# USBHub.net
KiCad netlist of a schematic drawn in Altium Designer
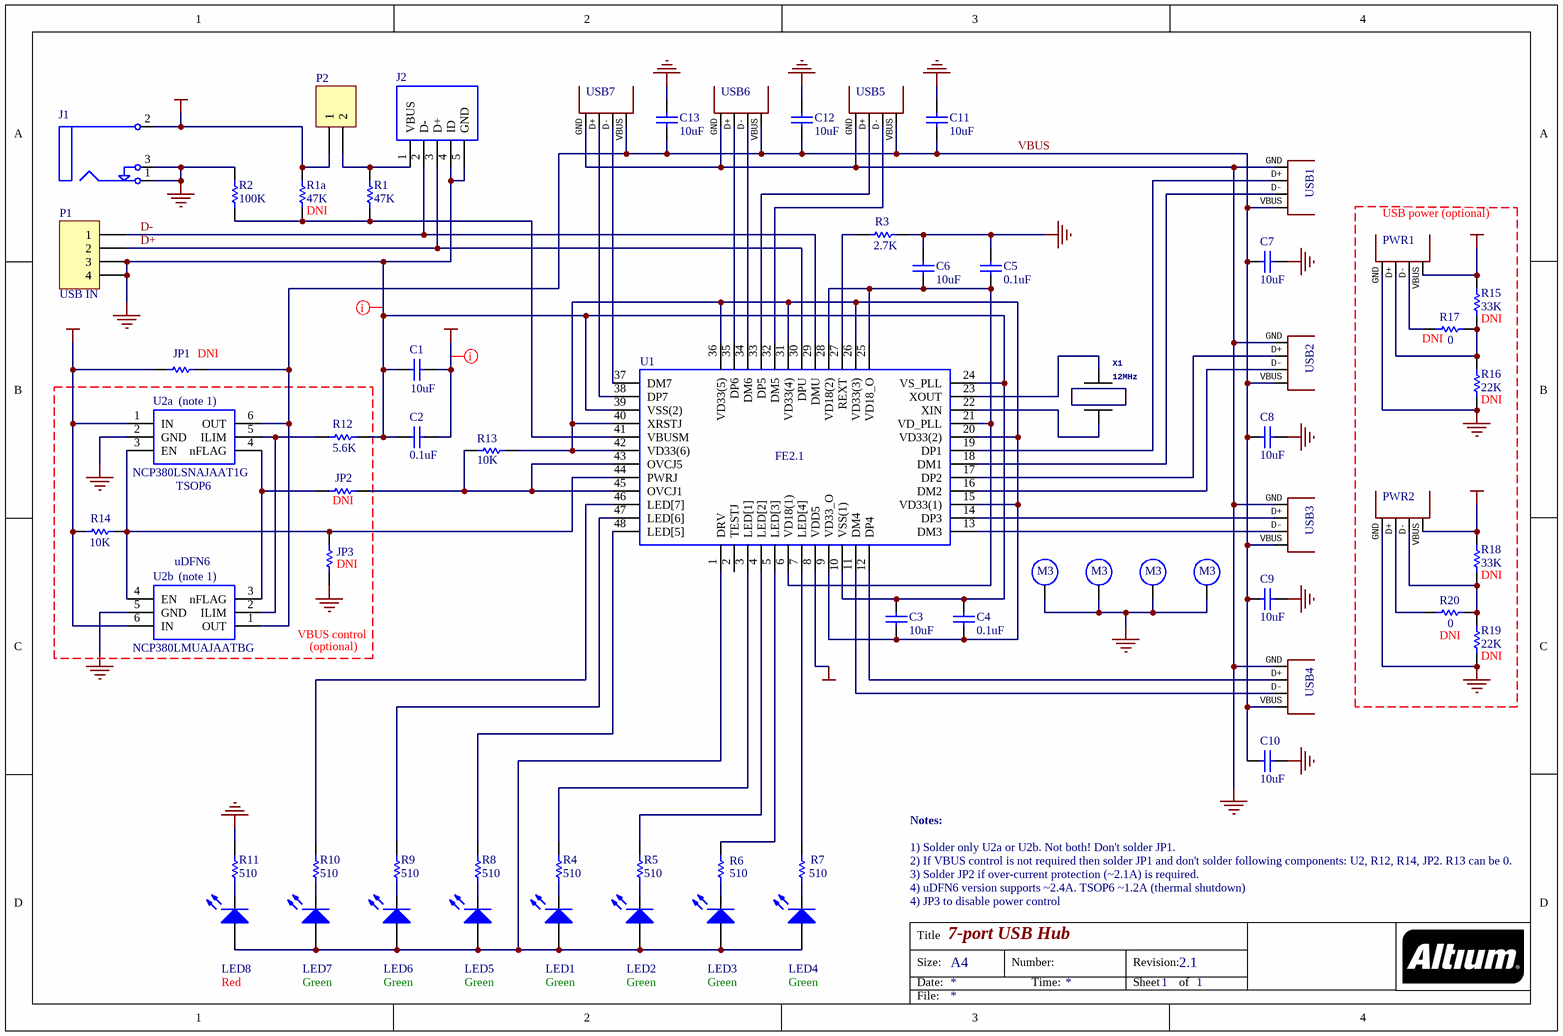
[diagram p0: USBHub.SchDoc]

(export (version "E")
  (design (tool "Eeschema 10.0.6"))
  (components
    (comp (ref "C1")
      (value "10uF")
      (footprint "C0805")
      (description "Ceramic Chip Capacitor - Standard")
      (fields (field (name "Comment") "C0805") (field (name "PUBLISHER") "Altium Limited"))
      (libsource (lib "KEMET Chip Capacitor") (part "C0805"))
    )
    (comp (ref "C2")
      (value "0.1uF")
      (footprint "C0805")
      (description "Ceramic Chip Capacitor - Standard")
      (fields (field (name "Comment") "C0805") (field (name "PUBLISHER") "Altium Limited"))
      (libsource (lib "KEMET Chip Capacitor") (part "C0805"))
    )
    (comp (ref "C3")
      (value "10uF")
      (footprint "C0805")
      (description "Ceramic Chip Capacitor - Standard")
      (fields (field (name "Comment") "C0805") (field (name "PUBLISHER") "Altium Limited"))
      (libsource (lib "KEMET Chip Capacitor") (part "C0805"))
    )
    (comp (ref "C4")
      (value "0.1uF")
      (footprint "C0805")
      (description "Ceramic Chip Capacitor - Standard")
      (fields (field (name "Comment") "C0805") (field (name "PUBLISHER") "Altium Limited"))
      (libsource (lib "KEMET Chip Capacitor") (part "C0805"))
    )
    (comp (ref "C5")
      (value "0.1uF")
      (footprint "C0805")
      (description "Ceramic Chip Capacitor - Standard")
      (fields (field (name "Comment") "C0805") (field (name "PUBLISHER") "Altium Limited"))
      (libsource (lib "KEMET Chip Capacitor") (part "C0805"))
    )
    (comp (ref "C6")
      (value "10uF")
      (footprint "C0805")
      (description "Ceramic Chip Capacitor - Standard")
      (fields (field (name "Comment") "C0805") (field (name "PUBLISHER") "Altium Limited"))
      (libsource (lib "KEMET Chip Capacitor") (part "C0805"))
    )
    (comp (ref "C7")
      (value "10uF")
      (footprint "C0805")
      (description "Ceramic Chip Capacitor - Standard")
      (fields (field (name "Comment") "C0805") (field (name "PUBLISHER") "Altium Limited"))
      (libsource (lib "KEMET Chip Capacitor") (part "C0805"))
    )
    (comp (ref "C8")
      (value "10uF")
      (footprint "C0805")
      (description "Ceramic Chip Capacitor - Standard")
      (fields (field (name "Comment") "C0805") (field (name "PUBLISHER") "Altium Limited"))
      (libsource (lib "KEMET Chip Capacitor") (part "C0805"))
    )
    (comp (ref "C9")
      (value "10uF")
      (footprint "C0805")
      (description "Ceramic Chip Capacitor - Standard")
      (fields (field (name "Comment") "C0805") (field (name "PUBLISHER") "Altium Limited"))
      (libsource (lib "KEMET Chip Capacitor") (part "C0805"))
    )
    (comp (ref "C10")
      (value "10uF")
      (footprint "C0805")
      (description "Ceramic Chip Capacitor - Standard")
      (fields (field (name "Comment") "C0805") (field (name "PUBLISHER") "Altium Limited"))
      (libsource (lib "KEMET Chip Capacitor") (part "C0805"))
    )
    (comp (ref "C11")
      (value "10uF")
      (footprint "C0805")
      (description "Ceramic Chip Capacitor - Standard")
      (fields (field (name "Comment") "C0805") (field (name "PUBLISHER") "Altium Limited"))
      (libsource (lib "KEMET Chip Capacitor") (part "C0805"))
    )
    (comp (ref "C12")
      (value "10uF")
      (footprint "C0805")
      (description "Ceramic Chip Capacitor - Standard")
      (fields (field (name "Comment") "C0805") (field (name "PUBLISHER") "Altium Limited"))
      (libsource (lib "KEMET Chip Capacitor") (part "C0805"))
    )
    (comp (ref "C13")
      (value "10uF")
      (footprint "C0805")
      (description "Ceramic Chip Capacitor - Standard")
      (fields (field (name "Comment") "C0805") (field (name "PUBLISHER") "Altium Limited"))
      (libsource (lib "KEMET Chip Capacitor") (part "C0805"))
    )
    (comp (ref "H1") (value "M3") (footprint "M3") (libsource (lib "lib") (part "M3")))
    (comp (ref "H2") (value "M3") (footprint "M3") (libsource (lib "lib") (part "M3")))
    (comp (ref "H3") (value "M3") (footprint "M3") (libsource (lib "lib") (part "M3")))
    (comp (ref "H4") (value "M3") (footprint "M3") (libsource (lib "lib") (part "M3")))
    (comp (ref "J1") (value "*") (footprint "PWR-2mm - DNI") (libsource (lib "lib") (part "Powerjack")))
    (comp (ref "J2")
      (value "MicroUSB SMT")
      (footprint "MicroUSB SMT v2")
      (fields
        (field (name "MANUFACTURER_PART_NUMBER") "47346-0001")
        (field (name "MOUSER PART NUMBER") "538-47346-0001")
        (field (name "RS PART NUMBER") "7025475P")
      )
      (libsource (lib "lib") (part "MicroUSB SMT"))
    )
    (comp (ref "JP1")
      (value "0")
      (footprint "R0805 - DNI")
      (fields (field (name "PUBLISHER") "Altium Limited"))
      (libsource (lib "lib") (part "R0805"))
    )
    (comp (ref "JP2")
      (value "0")
      (footprint "R0805 - DNI")
      (fields (field (name "PUBLISHER") "Altium Limited"))
      (libsource (lib "lib") (part "R0805"))
    )
    (comp (ref "JP3")
      (value "0")
      (footprint "R0805 - DNI")
      (fields (field (name "PUBLISHER") "Altium Limited"))
      (libsource (lib "lib") (part "R0805"))
    )
    (comp (ref "LED1")
      (value "Green")
      (footprint "LEDG0805")
      (description "Typical RED, GREEN, YELLOW, AMBER GaAs LED")
      (fields (field (name "PUBLISHER") "Altium Limited"))
      (libsource (lib "Miscellaneous Devices") (part "LED2"))
    )
    (comp (ref "LED2")
      (value "Green")
      (footprint "LEDG0805")
      (description "Typical RED, GREEN, YELLOW, AMBER GaAs LED")
      (fields (field (name "PUBLISHER") "Altium Limited"))
      (libsource (lib "Miscellaneous Devices") (part "LED2"))
    )
    (comp (ref "LED3")
      (value "Green")
      (footprint "LEDG0805")
      (description "Typical RED, GREEN, YELLOW, AMBER GaAs LED")
      (fields (field (name "PUBLISHER") "Altium Limited"))
      (libsource (lib "Miscellaneous Devices") (part "LED2"))
    )
    (comp (ref "LED4")
      (value "Green")
      (footprint "LEDG0805")
      (description "Typical RED, GREEN, YELLOW, AMBER GaAs LED")
      (fields (field (name "PUBLISHER") "Altium Limited"))
      (libsource (lib "Miscellaneous Devices") (part "LED2"))
    )
    (comp (ref "LED5")
      (value "Green")
      (footprint "LEDG0805")
      (description "Typical RED, GREEN, YELLOW, AMBER GaAs LED")
      (fields (field (name "PUBLISHER") "Altium Limited"))
      (libsource (lib "Miscellaneous Devices") (part "LED2"))
    )
    (comp (ref "LED6")
      (value "Green")
      (footprint "LEDG0805")
      (description "Typical RED, GREEN, YELLOW, AMBER GaAs LED")
      (fields (field (name "PUBLISHER") "Altium Limited"))
      (libsource (lib "Miscellaneous Devices") (part "LED2"))
    )
    (comp (ref "LED7")
      (value "Green")
      (footprint "LEDG0805")
      (description "Typical RED, GREEN, YELLOW, AMBER GaAs LED")
      (fields (field (name "PUBLISHER") "Altium Limited"))
      (libsource (lib "Miscellaneous Devices") (part "LED2"))
    )
    (comp (ref "LED8")
      (value "Red")
      (footprint "LEDR0805")
      (description "Typical RED, GREEN, YELLOW, AMBER GaAs LED")
      (fields (field (name "PUBLISHER") "Altium Limited"))
      (libsource (lib "Miscellaneous Devices") (part "LED2"))
    )
    (comp (ref "P1")
      (value "USB IN")
      (footprint "HDR1X4")
      (description "Header, 4-Pin")
      (fields (field (name "PUBLISHER") "Altium Limited"))
      (libsource (lib "Miscellaneous Connectors") (part "Header 4"))
    )
    (comp (ref "P2")
      (value "Header 2")
      (footprint "HDR1X2")
      (description "Header, 2-Pin")
      (fields (field (name "PUBLISHER") "Altium Limited"))
      (libsource (lib "Miscellaneous Connectors") (part "Header 2"))
    )
    (comp (ref "PWR1") (value "USBA-PTH") (footprint "USB-A-F-PTH") (libsource (lib "lib") (part "USBA-PTH")))
    (comp (ref "PWR2") (value "USBA-PTH") (footprint "USB-A-F-PTH") (libsource (lib "lib") (part "USBA-PTH")))
    (comp (ref "R1")
      (value "47K")
      (footprint "R0805")
      (fields (field (name "PUBLISHER") "Altium Limited"))
      (libsource (lib "lib") (part "R0805"))
    )
    (comp (ref "R1a")
      (value "47K")
      (footprint "R0805 - DNI")
      (fields (field (name "PUBLISHER") "Altium Limited"))
      (libsource (lib "lib") (part "R0805"))
    )
    (comp (ref "R2")
      (value "100K")
      (footprint "R0805")
      (fields (field (name "PUBLISHER") "Altium Limited"))
      (libsource (lib "lib") (part "R0805"))
    )
    (comp (ref "R3")
      (value "2.7K")
      (footprint "R0805")
      (fields (field (name "PUBLISHER") "Altium Limited"))
      (libsource (lib "lib") (part "R0805"))
    )
    (comp (ref "R4")
      (value "510")
      (footprint "R0805")
      (fields (field (name "PUBLISHER") "Altium Limited"))
      (libsource (lib "lib") (part "R0805"))
    )
    (comp (ref "R5")
      (value "510")
      (footprint "R0805")
      (fields (field (name "PUBLISHER") "Altium Limited"))
      (libsource (lib "lib") (part "R0805"))
    )
    (comp (ref "R6")
      (value "510")
      (footprint "R0805")
      (fields (field (name "PUBLISHER") "Altium Limited"))
      (libsource (lib "lib") (part "R0805"))
    )
    (comp (ref "R7")
      (value "510")
      (footprint "R0805")
      (fields (field (name "PUBLISHER") "Altium Limited"))
      (libsource (lib "lib") (part "R0805"))
    )
    (comp (ref "R8")
      (value "510")
      (footprint "R0805")
      (fields (field (name "PUBLISHER") "Altium Limited"))
      (libsource (lib "lib") (part "R0805"))
    )
    (comp (ref "R9")
      (value "510")
      (footprint "R0805")
      (fields (field (name "PUBLISHER") "Altium Limited"))
      (libsource (lib "lib") (part "R0805"))
    )
    (comp (ref "R10")
      (value "510")
      (footprint "R0805")
      (fields (field (name "PUBLISHER") "Altium Limited"))
      (libsource (lib "lib") (part "R0805"))
    )
    (comp (ref "R11")
      (value "510")
      (footprint "R0805")
      (fields (field (name "PUBLISHER") "Altium Limited"))
      (libsource (lib "lib") (part "R0805"))
    )
    (comp (ref "R12")
      (value "5.6K")
      (footprint "R0805")
      (fields (field (name "PUBLISHER") "Altium Limited"))
      (libsource (lib "lib") (part "R0805"))
    )
    (comp (ref "R13")
      (value "10K")
      (footprint "R0805")
      (fields (field (name "PUBLISHER") "Altium Limited"))
      (libsource (lib "lib") (part "R0805"))
    )
    (comp (ref "R14")
      (value "10K")
      (footprint "R0805")
      (fields (field (name "PUBLISHER") "Altium Limited"))
      (libsource (lib "lib") (part "R0805"))
    )
    (comp (ref "R15")
      (value "33K")
      (footprint "R0805 - DNI")
      (fields (field (name "PUBLISHER") "Altium Limited"))
      (libsource (lib "lib") (part "R0805 - DNI"))
    )
    (comp (ref "R16")
      (value "22K")
      (footprint "R0805 - DNI")
      (fields (field (name "PUBLISHER") "Altium Limited"))
      (libsource (lib "lib") (part "R0805 - DNI"))
    )
    (comp (ref "R17")
      (value "0")
      (footprint "R0805 - DNI")
      (fields (field (name "PUBLISHER") "Altium Limited"))
      (libsource (lib "lib") (part "R0805 - DNI"))
    )
    (comp (ref "R18")
      (value "33K")
      (footprint "R0805 - DNI")
      (fields (field (name "PUBLISHER") "Altium Limited"))
      (libsource (lib "lib") (part "R0805 - DNI"))
    )
    (comp (ref "R19")
      (value "22K")
      (footprint "R0805 - DNI")
      (fields (field (name "PUBLISHER") "Altium Limited"))
      (libsource (lib "lib") (part "R0805 - DNI"))
    )
    (comp (ref "R20")
      (value "0")
      (footprint "R0805 - DNI")
      (fields (field (name "PUBLISHER") "Altium Limited"))
      (libsource (lib "lib") (part "R0805 - DNI"))
    )
    (comp (ref "U1")
      (value "FE2.1")
      (footprint "LQFP48")
      (description "USB 2.0 HIGH SPEED 7-PORT HUB CONTROLLER")
      (fields (field (name "MANUFACTURER_PART_NUMBER") "FE2.1_QFP"))
      (libsource (lib "lib") (part "FE2.1_QFP"))
    )
    (comp (ref "U2a")
      (value "TSOP6")
      (footprint "SOT23-6_L")
      (fields (field (name "MANUFACTURER_PART_NUMBER") "NCP380LSNAJAAT1G"))
      (libsource (lib "lib") (part "NCP380-TSOP6"))
    )
    (comp (ref "U2b")
      (value "uDFN6")
      (footprint "uDFN6 2x2mm")
      (fields (field (name "MANUFACTURER_PART_NUMBER") "NCP380LMUAJAATBG"))
      (libsource (lib "lib") (part "NCP380-uDFN"))
    )
    (comp (ref "USB1") (value "USBA-PTH") (footprint "USB-A-F-PTH") (libsource (lib "lib") (part "USBA-PTH")))
    (comp (ref "USB2") (value "USBA-PTH") (footprint "USB-A-F-PTH") (libsource (lib "lib") (part "USBA-PTH")))
    (comp (ref "USB3") (value "USBA-PTH") (footprint "USB-A-F-PTH") (libsource (lib "lib") (part "USBA-PTH")))
    (comp (ref "USB4") (value "USBA-PTH") (footprint "USB-A-F-PTH") (libsource (lib "lib") (part "USBA-PTH")))
    (comp (ref "USB5") (value "USBA-PTH") (footprint "USB-A-F-PTH") (libsource (lib "lib") (part "USBA-PTH")))
    (comp (ref "USB6") (value "USBA-PTH") (footprint "USB-A-F-PTH") (libsource (lib "lib") (part "USBA-PTH")))
    (comp (ref "USB7") (value "USBA-PTH") (footprint "USB-A-F-PTH") (libsource (lib "lib") (part "USBA-PTH")))
    (comp (ref "X1")
      (value "12MHz")
      (footprint "XTAL_G5032")
      (description "PTH: ...   SMD: ...   Cylinder: CMR200T-32.768KDZBT")
      (libsource (lib "lib") (part "CRYSTALHC49UP"))
    )
  )
  (nets
    (net (code "1") (name "/D+") (class "Default")
      (node (ref "J2") (pin "3") (pinfunction "D+_3") (pintype "passive"))
      (node (ref "P1") (pin "2") (pinfunction "2_2") (pintype "passive"))
      (node (ref "U1") (pin "30") (pinfunction "DPU_30") (pintype "passive"))
    )
    (net (code "2") (name "/D-") (class "Default")
      (node (ref "J2") (pin "2") (pinfunction "D-_2") (pintype "passive"))
      (node (ref "P1") (pin "1") (pinfunction "1_1") (pintype "passive"))
      (node (ref "U1") (pin "29") (pinfunction "DMU_29") (pintype "passive"))
    )
    (net (code "3") (name "/VBUS") (class "Default")
      (node (ref "C10") (pin "1") (pinfunction "1_1") (pintype "passive"))
      (node (ref "C11") (pin "1") (pinfunction "1_1") (pintype "passive"))
      (node (ref "C12") (pin "1") (pinfunction "1_1") (pintype "passive"))
      (node (ref "C13") (pin "1") (pinfunction "1_1") (pintype "passive"))
      (node (ref "C7") (pin "1") (pinfunction "1_1") (pintype "passive"))
      (node (ref "C8") (pin "1") (pinfunction "1_1") (pintype "passive"))
      (node (ref "C9") (pin "1") (pinfunction "1_1") (pintype "passive"))
      (node (ref "JP1") (pin "1") (pinfunction "1_1") (pintype "passive"))
      (node (ref "U2a") (pin "6") (pinfunction "OUT_6") (pintype "passive"))
      (node (ref "U2b") (pin "1") (pinfunction "OUT_1") (pintype "passive"))
      (node (ref "USB1") (pin "VBUS") (pinfunction "VBUS_VBUS") (pintype "passive"))
      (node (ref "USB2") (pin "VBUS") (pinfunction "VBUS_VBUS") (pintype "passive"))
      (node (ref "USB3") (pin "VBUS") (pinfunction "VBUS_VBUS") (pintype "passive"))
      (node (ref "USB4") (pin "VBUS") (pinfunction "VBUS_VBUS") (pintype "passive"))
      (node (ref "USB5") (pin "VBUS") (pinfunction "VBUS_VBUS") (pintype "passive"))
      (node (ref "USB6") (pin "VBUS") (pinfunction "VBUS_VBUS") (pintype "passive"))
      (node (ref "USB7") (pin "VBUS") (pinfunction "VBUS_VBUS") (pintype "passive"))
    )
    (net (code "4") (name "GND") (class "Default")
      (node (ref "C1") (pin "2") (pinfunction "2_2") (pintype "passive"))
      (node (ref "C10") (pin "2") (pinfunction "2_2") (pintype "passive"))
      (node (ref "C11") (pin "2") (pinfunction "2_2") (pintype "passive"))
      (node (ref "C12") (pin "2") (pinfunction "2_2") (pintype "passive"))
      (node (ref "C13") (pin "2") (pinfunction "2_2") (pintype "passive"))
      (node (ref "C2") (pin "2") (pinfunction "2_2") (pintype "passive"))
      (node (ref "C3") (pin "2") (pinfunction "2_2") (pintype "passive"))
      (node (ref "C4") (pin "2") (pinfunction "2_2") (pintype "passive"))
      (node (ref "C5") (pin "2") (pinfunction "2_2") (pintype "passive"))
      (node (ref "C6") (pin "2") (pinfunction "2_2") (pintype "passive"))
      (node (ref "C7") (pin "2") (pinfunction "2_2") (pintype "passive"))
      (node (ref "C8") (pin "2") (pinfunction "2_2") (pintype "passive"))
      (node (ref "C9") (pin "2") (pinfunction "2_2") (pintype "passive"))
      (node (ref "H1") (pin "1") (pinfunction "1_1") (pintype "passive"))
      (node (ref "H2") (pin "1") (pinfunction "1_1") (pintype "passive"))
      (node (ref "H3") (pin "1") (pinfunction "1_1") (pintype "passive"))
      (node (ref "H4") (pin "1") (pinfunction "1_1") (pintype "passive"))
      (node (ref "J1") (pin "1") (pinfunction "1_1") (pintype "passive"))
      (node (ref "J1") (pin "3") (pinfunction "3_3") (pintype "passive"))
      (node (ref "J2") (pin "4") (pinfunction "ID_4") (pintype "passive"))
      (node (ref "J2") (pin "5") (pinfunction "GND_5") (pintype "passive"))
      (node (ref "JP3") (pin "2") (pinfunction "2_2") (pintype "passive"))
      (node (ref "P1") (pin "3") (pinfunction "3_3") (pintype "passive"))
      (node (ref "P1") (pin "4") (pinfunction "4_4") (pintype "passive"))
      (node (ref "PWR1") (pin "GND") (pinfunction "GND_GND") (pintype "passive"))
      (node (ref "PWR2") (pin "GND") (pinfunction "GND_GND") (pintype "passive"))
      (node (ref "R11") (pin "2") (pinfunction "2_2") (pintype "passive"))
      (node (ref "R12") (pin "2") (pinfunction "2_2") (pintype "passive"))
      (node (ref "R16") (pin "2") (pinfunction "2_2") (pintype "passive"))
      (node (ref "R19") (pin "2") (pinfunction "2_2") (pintype "passive"))
      (node (ref "R2") (pin "1") (pinfunction "1_1") (pintype "passive"))
      (node (ref "R3") (pin "2") (pinfunction "2_2") (pintype "passive"))
      (node (ref "U1") (pin "10") (pinfunction "VSS(1)_10") (pintype "passive"))
      (node (ref "U1") (pin "24") (pinfunction "VS_PLL_24") (pintype "passive"))
      (node (ref "U1") (pin "39") (pinfunction "VSS(2)_39") (pintype "passive"))
      (node (ref "U2a") (pin "2") (pinfunction "GND_2") (pintype "passive"))
      (node (ref "U2b") (pin "5") (pinfunction "GND_5") (pintype "passive"))
      (node (ref "USB1") (pin "GND") (pinfunction "GND_GND") (pintype "passive"))
      (node (ref "USB2") (pin "GND") (pinfunction "GND_GND") (pintype "passive"))
      (node (ref "USB3") (pin "GND") (pinfunction "GND_GND") (pintype "passive"))
      (node (ref "USB4") (pin "GND") (pinfunction "GND_GND") (pintype "passive"))
      (node (ref "USB5") (pin "GND") (pinfunction "GND_GND") (pintype "passive"))
      (node (ref "USB6") (pin "GND") (pinfunction "GND_GND") (pintype "passive"))
      (node (ref "USB7") (pin "GND") (pinfunction "GND_GND") (pintype "passive"))
    )
    (net (code "5") (name "Net-(J2-VBUS)") (class "Default")
      (node (ref "J2") (pin "1") (pinfunction "VBUS_1") (pintype "passive"))
      (node (ref "P2") (pin "2") (pinfunction "2_2") (pintype "passive"))
      (node (ref "R1") (pin "1") (pinfunction "1_1") (pintype "passive"))
    )
    (net (code "6") (name "Net-(LED1-A)") (class "Default")
      (node (ref "LED1") (pin "1") (pinfunction "A_1") (pintype "passive"))
      (node (ref "LED2") (pin "1") (pinfunction "A_1") (pintype "passive"))
      (node (ref "LED3") (pin "1") (pinfunction "A_1") (pintype "passive"))
      (node (ref "LED4") (pin "1") (pinfunction "A_1") (pintype "passive"))
      (node (ref "LED5") (pin "1") (pinfunction "A_1") (pintype "passive"))
      (node (ref "LED6") (pin "1") (pinfunction "A_1") (pintype "passive"))
      (node (ref "LED7") (pin "1") (pinfunction "A_1") (pintype "passive"))
      (node (ref "LED8") (pin "1") (pinfunction "A_1") (pintype "passive"))
      (node (ref "U1") (pin "1") (pinfunction "DRV_1") (pintype "passive"))
    )
    (net (code "7") (name "Net-(LED1-K)") (class "Default")
      (node (ref "LED1") (pin "2") (pinfunction "K_2") (pintype "passive"))
      (node (ref "R4") (pin "2") (pinfunction "2_2") (pintype "passive"))
    )
    (net (code "8") (name "Net-(LED2-K)") (class "Default")
      (node (ref "LED2") (pin "2") (pinfunction "K_2") (pintype "passive"))
      (node (ref "R5") (pin "2") (pinfunction "2_2") (pintype "passive"))
    )
    (net (code "9") (name "Net-(LED3-K)") (class "Default")
      (node (ref "LED3") (pin "2") (pinfunction "K_2") (pintype "passive"))
      (node (ref "R6") (pin "2") (pinfunction "2_2") (pintype "passive"))
    )
    (net (code "10") (name "Net-(LED4-K)") (class "Default")
      (node (ref "LED4") (pin "2") (pinfunction "K_2") (pintype "passive"))
      (node (ref "R7") (pin "2") (pinfunction "2_2") (pintype "passive"))
    )
    (net (code "11") (name "Net-(LED5-K)") (class "Default")
      (node (ref "LED5") (pin "2") (pinfunction "K_2") (pintype "passive"))
      (node (ref "R8") (pin "2") (pinfunction "2_2") (pintype "passive"))
    )
    (net (code "12") (name "Net-(LED6-K)") (class "Default")
      (node (ref "LED6") (pin "2") (pinfunction "K_2") (pintype "passive"))
      (node (ref "R9") (pin "2") (pinfunction "2_2") (pintype "passive"))
    )
    (net (code "13") (name "Net-(LED7-K)") (class "Default")
      (node (ref "LED7") (pin "2") (pinfunction "K_2") (pintype "passive"))
      (node (ref "R10") (pin "2") (pinfunction "2_2") (pintype "passive"))
    )
    (net (code "14") (name "Net-(LED8-K)") (class "Default")
      (node (ref "LED8") (pin "2") (pinfunction "K_2") (pintype "passive"))
      (node (ref "R11") (pin "1") (pinfunction "1_1") (pintype "passive"))
    )
    (net (code "15") (name "Net-(PWR1-PadD+)") (class "Default")
      (node (ref "PWR1") (pin "D+") (pinfunction "D+_D+") (pintype "passive"))
      (node (ref "R15") (pin "2") (pinfunction "2_2") (pintype "passive"))
      (node (ref "R16") (pin "1") (pinfunction "1_1") (pintype "passive"))
      (node (ref "R17") (pin "2") (pinfunction "2_2") (pintype "passive"))
    )
    (net (code "16") (name "Net-(PWR1-PadD-)") (class "Default")
      (node (ref "PWR1") (pin "D-") (pinfunction "D-_D-") (pintype "passive"))
      (node (ref "R17") (pin "1") (pinfunction "1_1") (pintype "passive"))
    )
    (net (code "17") (name "Net-(PWR2-PadD+)") (class "Default")
      (node (ref "PWR2") (pin "D+") (pinfunction "D+_D+") (pintype "passive"))
      (node (ref "R20") (pin "1") (pinfunction "1_1") (pintype "passive"))
    )
    (net (code "18") (name "Net-(PWR2-PadD-)") (class "Default")
      (node (ref "PWR2") (pin "D-") (pinfunction "D-_D-") (pintype "passive"))
      (node (ref "R18") (pin "2") (pinfunction "2_2") (pintype "passive"))
      (node (ref "R19") (pin "1") (pinfunction "1_1") (pintype "passive"))
      (node (ref "R20") (pin "2") (pinfunction "2_2") (pintype "passive"))
    )
    (net (code "19") (name "Net-(U1-DM1)") (class "Default")
      (node (ref "U1") (pin "18") (pinfunction "DM1_18") (pintype "passive"))
      (node (ref "USB1") (pin "D-") (pinfunction "D-_D-") (pintype "passive"))
    )
    (net (code "20") (name "Net-(U1-DM2)") (class "Default")
      (node (ref "U1") (pin "16") (pinfunction "DM2_16") (pintype "passive"))
      (node (ref "USB2") (pin "D-") (pinfunction "D-_D-") (pintype "passive"))
    )
    (net (code "21") (name "Net-(U1-DM3)") (class "Default")
      (node (ref "U1") (pin "13") (pinfunction "DM3_13") (pintype "passive"))
      (node (ref "USB3") (pin "D-") (pinfunction "D-_D-") (pintype "passive"))
    )
    (net (code "22") (name "Net-(U1-DM4)") (class "Default")
      (node (ref "U1") (pin "11") (pinfunction "DM4_11") (pintype "passive"))
      (node (ref "USB4") (pin "D-") (pinfunction "D-_D-") (pintype "passive"))
    )
    (net (code "23") (name "Net-(U1-DM5)") (class "Default")
      (node (ref "U1") (pin "32") (pinfunction "DM5_32") (pintype "passive"))
      (node (ref "USB5") (pin "D-") (pinfunction "D-_D-") (pintype "passive"))
    )
    (net (code "24") (name "Net-(U1-DM6)") (class "Default")
      (node (ref "U1") (pin "34") (pinfunction "DM6_34") (pintype "passive"))
      (node (ref "USB6") (pin "D-") (pinfunction "D-_D-") (pintype "passive"))
    )
    (net (code "25") (name "Net-(U1-DM7)") (class "Default")
      (node (ref "U1") (pin "37") (pinfunction "DM7_37") (pintype "passive"))
      (node (ref "USB7") (pin "D-") (pinfunction "D-_D-") (pintype "passive"))
    )
    (net (code "26") (name "Net-(U1-DP1)") (class "Default")
      (node (ref "U1") (pin "19") (pinfunction "DP1_19") (pintype "passive"))
      (node (ref "USB1") (pin "D+") (pinfunction "D+_D+") (pintype "passive"))
    )
    (net (code "27") (name "Net-(U1-DP2)") (class "Default")
      (node (ref "U1") (pin "17") (pinfunction "DP2_17") (pintype "passive"))
      (node (ref "USB2") (pin "D+") (pinfunction "D+_D+") (pintype "passive"))
    )
    (net (code "28") (name "Net-(U1-DP3)") (class "Default")
      (node (ref "U1") (pin "14") (pinfunction "DP3_14") (pintype "passive"))
      (node (ref "USB3") (pin "D+") (pinfunction "D+_D+") (pintype "passive"))
    )
    (net (code "29") (name "Net-(U1-DP4)") (class "Default")
      (node (ref "U1") (pin "12") (pinfunction "DP4_12") (pintype "passive"))
      (node (ref "USB4") (pin "D+") (pinfunction "D+_D+") (pintype "passive"))
    )
    (net (code "30") (name "Net-(U1-DP5)") (class "Default")
      (node (ref "U1") (pin "33") (pinfunction "DP5_33") (pintype "passive"))
      (node (ref "USB5") (pin "D+") (pinfunction "D+_D+") (pintype "passive"))
    )
    (net (code "31") (name "Net-(U1-DP6)") (class "Default")
      (node (ref "U1") (pin "35") (pinfunction "DP6_35") (pintype "passive"))
      (node (ref "USB6") (pin "D+") (pinfunction "D+_D+") (pintype "passive"))
    )
    (net (code "32") (name "Net-(U1-DP7)") (class "Default")
      (node (ref "U1") (pin "38") (pinfunction "DP7_38") (pintype "passive"))
      (node (ref "USB7") (pin "D+") (pinfunction "D+_D+") (pintype "passive"))
    )
    (net (code "33") (name "Net-(U1-LED[1])") (class "Default")
      (node (ref "R4") (pin "1") (pinfunction "1_1") (pintype "passive"))
      (node (ref "U1") (pin "3") (pinfunction "LED[1]_3") (pintype "passive"))
    )
    (net (code "34") (name "Net-(U1-LED[2])") (class "Default")
      (node (ref "R5") (pin "1") (pinfunction "1_1") (pintype "passive"))
      (node (ref "U1") (pin "4") (pinfunction "LED[2]_4") (pintype "passive"))
    )
    (net (code "35") (name "Net-(U1-LED[3])") (class "Default")
      (node (ref "R6") (pin "1") (pinfunction "1_1") (pintype "passive"))
      (node (ref "U1") (pin "5") (pinfunction "LED[3]_5") (pintype "passive"))
    )
    (net (code "36") (name "Net-(U1-LED[4])") (class "Default")
      (node (ref "R7") (pin "1") (pinfunction "1_1") (pintype "passive"))
      (node (ref "U1") (pin "7") (pinfunction "LED[4]_7") (pintype "passive"))
    )
    (net (code "37") (name "Net-(U1-LED[5])") (class "Default")
      (node (ref "R8") (pin "1") (pinfunction "1_1") (pintype "passive"))
      (node (ref "U1") (pin "48") (pinfunction "LED[5]_48") (pintype "passive"))
    )
    (net (code "38") (name "Net-(U1-LED[6])") (class "Default")
      (node (ref "R9") (pin "1") (pinfunction "1_1") (pintype "passive"))
      (node (ref "U1") (pin "47") (pinfunction "LED[6]_47") (pintype "passive"))
    )
    (net (code "39") (name "Net-(U1-LED[7])") (class "Default")
      (node (ref "R10") (pin "1") (pinfunction "1_1") (pintype "passive"))
      (node (ref "U1") (pin "46") (pinfunction "LED[7]_46") (pintype "passive"))
    )
    (net (code "40") (name "Net-(U1-OVCJ1)") (class "Default")
      (node (ref "JP2") (pin "1") (pinfunction "1_1") (pintype "passive"))
      (node (ref "R13") (pin "2") (pinfunction "2_2") (pintype "passive"))
      (node (ref "U1") (pin "43") (pinfunction "OVCJ5_43") (pintype "passive"))
      (node (ref "U1") (pin "45") (pinfunction "OVCJ1_45") (pintype "passive"))
    )
    (net (code "41") (name "Net-(U1-PWRJ)") (class "Default")
      (node (ref "JP3") (pin "1") (pinfunction "1_1") (pintype "passive"))
      (node (ref "R14") (pin "1") (pinfunction "1_1") (pintype "passive"))
      (node (ref "U1") (pin "44") (pinfunction "PWRJ_44") (pintype "passive"))
      (node (ref "U2a") (pin "3") (pinfunction "EN_3") (pintype "passive"))
      (node (ref "U2b") (pin "4") (pinfunction "EN_4") (pintype "passive"))
    )
    (net (code "42") (name "Net-(U1-REXT)") (class "Default")
      (node (ref "R3") (pin "1") (pinfunction "1_1") (pintype "passive"))
      (node (ref "U1") (pin "27") (pinfunction "REXT_27") (pintype "passive"))
    )
    (net (code "43") (name "Net-(U1-VBUSM)") (class "Default")
      (node (ref "R1") (pin "2") (pinfunction "2_2") (pintype "passive"))
      (node (ref "R1a") (pin "2") (pinfunction "2_2") (pintype "passive"))
      (node (ref "R2") (pin "2") (pinfunction "2_2") (pintype "passive"))
      (node (ref "U1") (pin "41") (pinfunction "VBUSM_41") (pintype "passive"))
    )
    (net (code "44") (name "Net-(U1-VD18(1))") (class "Default")
      (node (ref "C5") (pin "1") (pinfunction "1_1") (pintype "passive"))
      (node (ref "C6") (pin "1") (pinfunction "1_1") (pintype "passive"))
      (node (ref "U1") (pin "21") (pinfunction "VD_PLL_21") (pintype "passive"))
      (node (ref "U1") (pin "25") (pinfunction "VD18_O_25") (pintype "passive"))
      (node (ref "U1") (pin "28") (pinfunction "VD18(2)_28") (pintype "passive"))
      (node (ref "U1") (pin "6") (pinfunction "VD18(1)_6") (pintype "passive"))
    )
    (net (code "45") (name "Net-(U1-VD33(1))") (class "Default")
      (node (ref "C3") (pin "1") (pinfunction "1_1") (pintype "passive"))
      (node (ref "C4") (pin "1") (pinfunction "1_1") (pintype "passive"))
      (node (ref "R13") (pin "1") (pinfunction "1_1") (pintype "passive"))
      (node (ref "U1") (pin "15") (pinfunction "VD33(1)_15") (pintype "passive"))
      (node (ref "U1") (pin "20") (pinfunction "VD33(2)_20") (pintype "passive"))
      (node (ref "U1") (pin "26") (pinfunction "VD33(3)_26") (pintype "passive"))
      (node (ref "U1") (pin "31") (pinfunction "VD33(4)_31") (pintype "passive"))
      (node (ref "U1") (pin "36") (pinfunction "VD33(5)_36") (pintype "passive"))
      (node (ref "U1") (pin "40") (pinfunction "XRSTJ_40") (pintype "passive"))
      (node (ref "U1") (pin "42") (pinfunction "VD33(6)_42") (pintype "passive"))
      (node (ref "U1") (pin "9") (pinfunction "VD33_O_9") (pintype "passive"))
    )
    (net (code "46") (name "Net-(U1-XIN)") (class "Default")
      (node (ref "U1") (pin "22") (pinfunction "XIN_22") (pintype "passive"))
      (node (ref "X1") (pin "2") (pinfunction "2_2") (pintype "passive"))
    )
    (net (code "47") (name "Net-(U1-XOUT)") (class "Default")
      (node (ref "U1") (pin "23") (pinfunction "XOUT_23") (pintype "passive"))
      (node (ref "X1") (pin "1") (pinfunction "1_1") (pintype "passive"))
    )
    (net (code "48") (name "Net-(U2a-ILIM)") (class "Default")
      (node (ref "R12") (pin "1") (pinfunction "1_1") (pintype "passive"))
      (node (ref "U2a") (pin "5") (pinfunction "ILIM_5") (pintype "passive"))
      (node (ref "U2b") (pin "2") (pinfunction "ILIM_2") (pintype "passive"))
    )
    (net (code "49") (name "Net-(U2a-nFLAG)") (class "Default")
      (node (ref "JP2") (pin "2") (pinfunction "2_2") (pintype "passive"))
      (node (ref "U2a") (pin "4") (pinfunction "nFLAG_4") (pintype "passive"))
      (node (ref "U2b") (pin "3") (pinfunction "nFLAG_3") (pintype "passive"))
    )
    (net (code "50") (name "VCC") (class "Default")
      (node (ref "C1") (pin "1") (pinfunction "1_1") (pintype "passive"))
      (node (ref "C2") (pin "1") (pinfunction "1_1") (pintype "passive"))
      (node (ref "J1") (pin "2") (pinfunction "2_2") (pintype "passive"))
      (node (ref "JP1") (pin "2") (pinfunction "2_2") (pintype "passive"))
      (node (ref "P2") (pin "1") (pinfunction "1_1") (pintype "passive"))
      (node (ref "PWR1") (pin "VBUS") (pinfunction "VBUS_VBUS") (pintype "passive"))
      (node (ref "PWR2") (pin "VBUS") (pinfunction "VBUS_VBUS") (pintype "passive"))
      (node (ref "R14") (pin "2") (pinfunction "2_2") (pintype "passive"))
      (node (ref "R15") (pin "1") (pinfunction "1_1") (pintype "passive"))
      (node (ref "R18") (pin "1") (pinfunction "1_1") (pintype "passive"))
      (node (ref "R1a") (pin "1") (pinfunction "1_1") (pintype "passive"))
      (node (ref "U1") (pin "8") (pinfunction "VDD5_8") (pintype "passive"))
      (node (ref "U2a") (pin "1") (pinfunction "IN_1") (pintype "passive"))
      (node (ref "U2b") (pin "6") (pinfunction "IN_6") (pintype "passive"))
    )
    (net (code "51") (name "unconnected-(U1-TESTJ-Pad2)") (class "Default")
      (node (ref "U1") (pin "2") (pinfunction "TESTJ_2") (pintype "passive"))
    )
  )
)
